# Arduino-Pro-Mini-RasPi.net
KiCad netlist of a schematic drawn in EAGLE
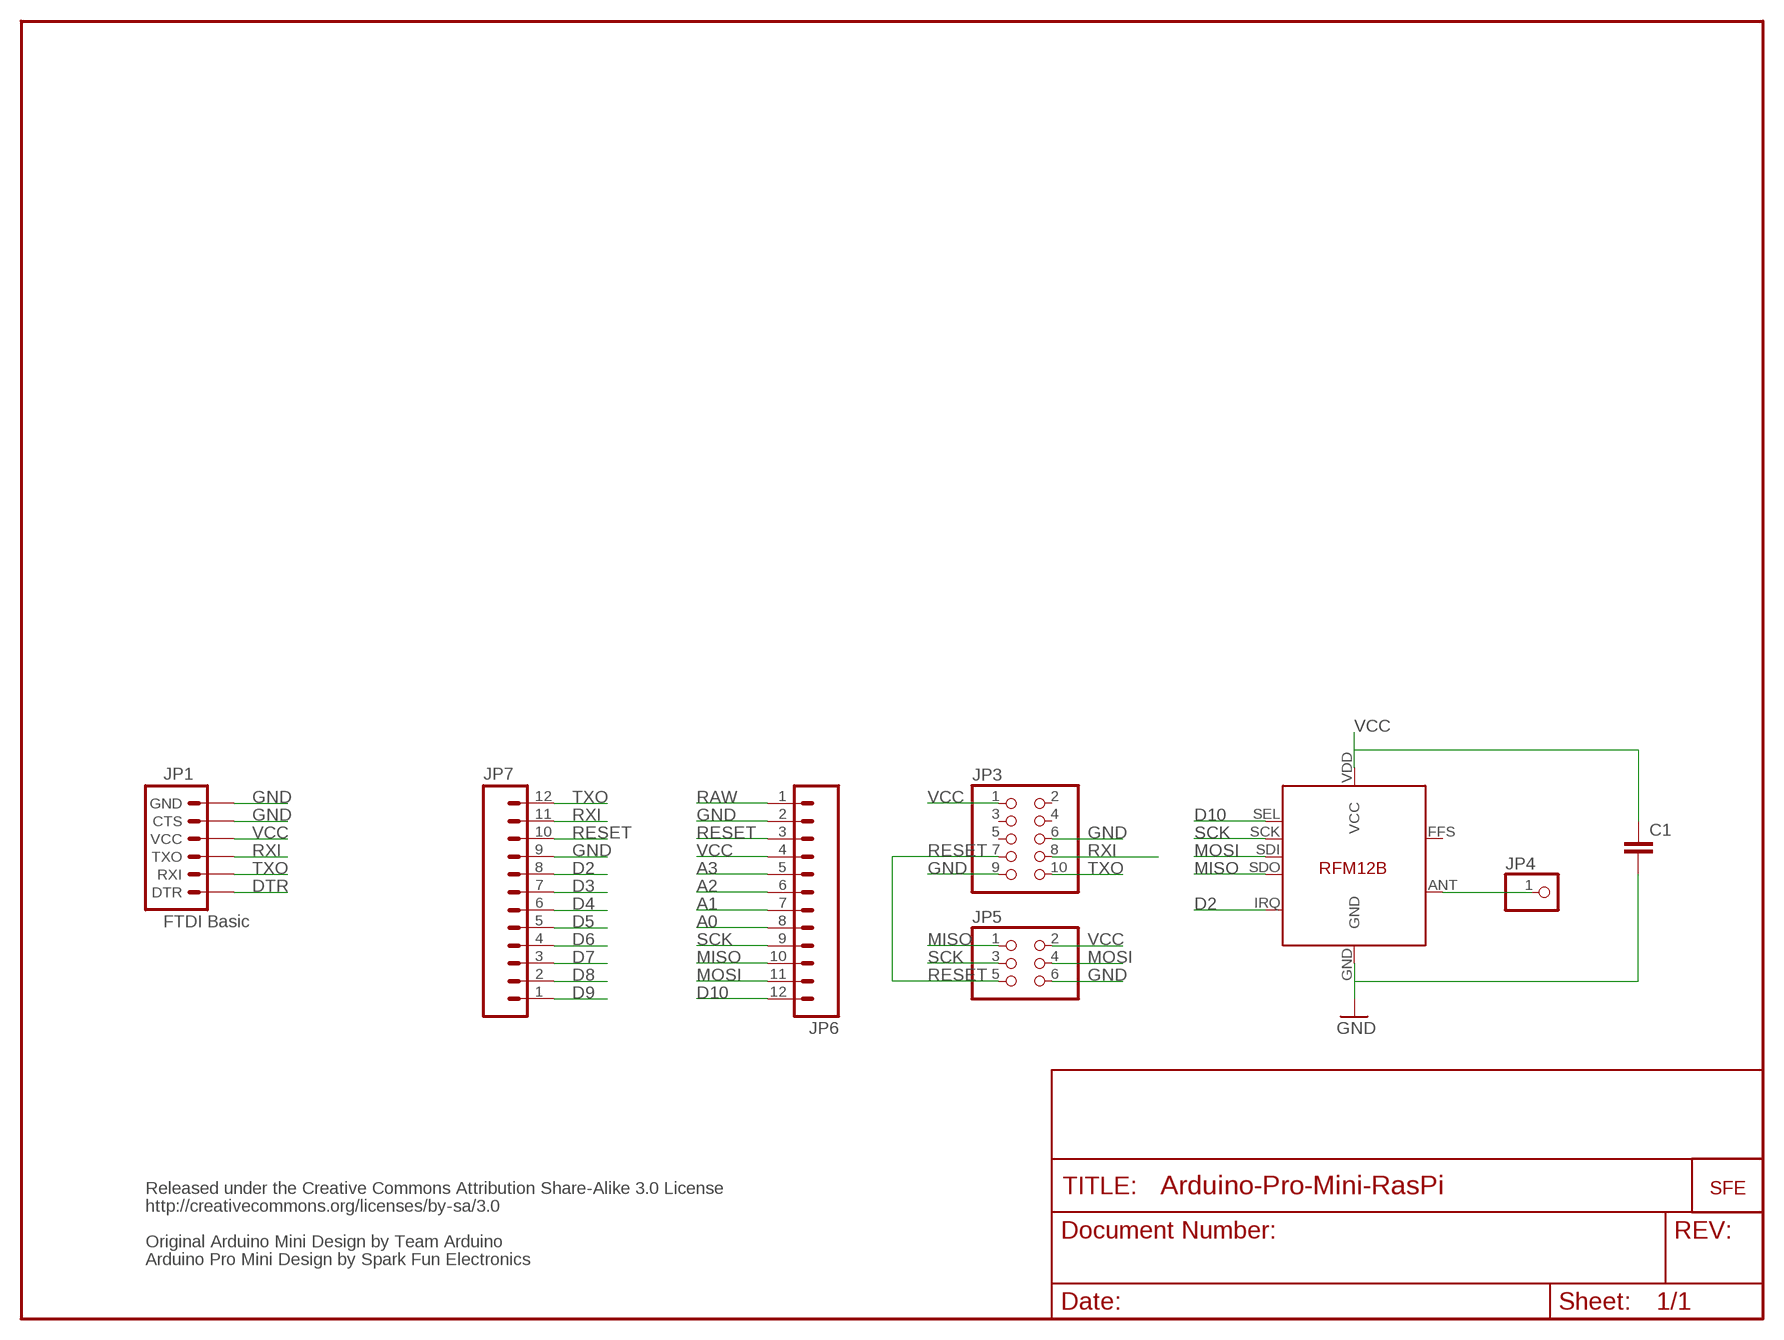
[diagram p0: schematic, sheet 1]

(export (version "E")
  (design (tool "Eeschema 10.0.6"))
  (components
    (comp (ref "C1")
      (value "C-EUC0805K")
      (footprint "eagle-import:C0805K")
      (libsource (lib "eagle-import") (part "C-EUC0805K"))
    )
    (comp (ref "JP1")
      (value "FTDI Basic")
      (footprint "eagle-import:1X06")
      (libsource (lib "eagle-import") (part "ARDUINO_SERIAL_PROGRAMPTH"))
    )
    (comp (ref "JP3")
      (value "PINHD-2X5")
      (footprint "eagle-import:2X05")
      (libsource (lib "eagle-import") (part "PINHD-2X5"))
    )
    (comp (ref "JP4")
      (value "PINHD-1X1")
      (footprint "eagle-import:1X01")
      (libsource (lib "eagle-import") (part "PINHD-1X1"))
    )
    (comp (ref "JP5")
      (value "PINHD-2X3_2.54-SMD")
      (footprint "eagle-import:2X03SMD")
      (libsource (lib "eagle-import") (part "PINHD-2X3_2.54-SMD"))
    )
    (comp (ref "JP6")
      (value "M12PTH")
      (footprint "eagle-import:1X12")
      (libsource (lib "eagle-import") (part "M12PTH"))
    )
    (comp (ref "JP7")
      (value "M12PTH")
      (footprint "eagle-import:1X12")
      (libsource (lib "eagle-import") (part "M12PTH"))
    )
    (comp (ref "U$3")
      (value "RFM12B")
      (footprint "eagle-import:RFM12B")
      (libsource (lib "eagle-import") (part "RFM12B"))
    )
    (comp (ref "U$11")
      (value "LOGO-SFENEW")
      (footprint "eagle-import:SFE-NEW-WEBLOGO")
      (libsource (lib "eagle-import") (part "LOGO-SFENEW"))
    )
  )
  (nets
    (net (code "1") (name "/A0") (class "Default")
      (node (ref "JP6") (pin "8") (pinfunction "8_8") (pintype "passive"))
    )
    (net (code "2") (name "/A1") (class "Default")
      (node (ref "JP6") (pin "7") (pinfunction "7_7") (pintype "passive"))
    )
    (net (code "3") (name "/A2") (class "Default")
      (node (ref "JP6") (pin "6") (pinfunction "6_6") (pintype "passive"))
    )
    (net (code "4") (name "/A3") (class "Default")
      (node (ref "JP6") (pin "5") (pinfunction "5_5") (pintype "passive"))
    )
    (net (code "5") (name "/D2") (class "Default")
      (node (ref "JP7") (pin "8") (pinfunction "8_8") (pintype "passive"))
      (node (ref "U$3") (pin "IRQ") (pinfunction "IRQ_IRQ") (pintype "open_collector"))
    )
    (net (code "6") (name "/D3") (class "Default")
      (node (ref "JP7") (pin "7") (pinfunction "7_7") (pintype "passive"))
    )
    (net (code "7") (name "/D4") (class "Default")
      (node (ref "JP7") (pin "6") (pinfunction "6_6") (pintype "passive"))
    )
    (net (code "8") (name "/D5") (class "Default")
      (node (ref "JP7") (pin "5") (pinfunction "5_5") (pintype "passive"))
    )
    (net (code "9") (name "/D6") (class "Default")
      (node (ref "JP7") (pin "4") (pinfunction "4_4") (pintype "passive"))
    )
    (net (code "10") (name "/D7") (class "Default")
      (node (ref "JP7") (pin "3") (pinfunction "3_3") (pintype "passive"))
    )
    (net (code "11") (name "/D8") (class "Default")
      (node (ref "JP7") (pin "2") (pinfunction "2_2") (pintype "passive"))
    )
    (net (code "12") (name "/D9") (class "Default")
      (node (ref "JP7") (pin "1") (pinfunction "1_1") (pintype "passive"))
    )
    (net (code "13") (name "/D10") (class "Default")
      (node (ref "JP6") (pin "12") (pinfunction "12_12") (pintype "passive"))
      (node (ref "U$3") (pin "SEL") (pinfunction "SEL_SEL") (pintype "input"))
    )
    (net (code "14") (name "/DTR") (class "Default")
      (node (ref "JP1") (pin "1") (pinfunction "DTR_1") (pintype "passive"))
    )
    (net (code "15") (name "/MISO") (class "Default")
      (node (ref "JP5") (pin "1") (pinfunction "1_1") (pintype "passive"))
      (node (ref "JP6") (pin "10") (pinfunction "10_10") (pintype "passive"))
      (node (ref "U$3") (pin "SDO") (pinfunction "SDO_SDO") (pintype "output"))
    )
    (net (code "16") (name "/MOSI") (class "Default")
      (node (ref "JP5") (pin "4") (pinfunction "4_4") (pintype "passive"))
      (node (ref "JP6") (pin "11") (pinfunction "11_11") (pintype "passive"))
      (node (ref "U$3") (pin "SDI") (pinfunction "SDI_SDI") (pintype "input"))
    )
    (net (code "17") (name "/RAW") (class "Default")
      (node (ref "JP6") (pin "1") (pinfunction "1_1") (pintype "passive"))
    )
    (net (code "18") (name "/RESET") (class "Default")
      (node (ref "JP3") (pin "7") (pinfunction "7_7") (pintype "passive"))
      (node (ref "JP5") (pin "5") (pinfunction "5_5") (pintype "passive"))
      (node (ref "JP6") (pin "3") (pinfunction "3_3") (pintype "passive"))
      (node (ref "JP7") (pin "10") (pinfunction "10_10") (pintype "passive"))
    )
    (net (code "19") (name "/RXI") (class "Default")
      (node (ref "JP1") (pin "3") (pinfunction "TXO_3") (pintype "passive"))
      (node (ref "JP3") (pin "8") (pinfunction "8_8") (pintype "passive"))
      (node (ref "JP7") (pin "11") (pinfunction "11_11") (pintype "passive"))
    )
    (net (code "20") (name "/SCK") (class "Default")
      (node (ref "JP5") (pin "3") (pinfunction "3_3") (pintype "passive"))
      (node (ref "JP6") (pin "9") (pinfunction "9_9") (pintype "passive"))
      (node (ref "U$3") (pin "SCK") (pinfunction "SCK_SCK") (pintype "input"))
    )
    (net (code "21") (name "/TXO") (class "Default")
      (node (ref "JP1") (pin "2") (pinfunction "RXI_2") (pintype "passive"))
      (node (ref "JP3") (pin "10") (pinfunction "10_10") (pintype "passive"))
      (node (ref "JP7") (pin "12") (pinfunction "12_12") (pintype "passive"))
    )
    (net (code "22") (name "/VCC") (class "Default")
      (node (ref "C1") (pin "1") (pinfunction "1_1") (pintype "passive"))
      (node (ref "JP1") (pin "4") (pinfunction "VCC_4") (pintype "passive"))
      (node (ref "JP3") (pin "1") (pinfunction "1_1") (pintype "passive"))
      (node (ref "JP5") (pin "2") (pinfunction "2_2") (pintype "passive"))
      (node (ref "JP6") (pin "4") (pinfunction "4_4") (pintype "passive"))
      (node (ref "U$3") (pin "VDD") (pinfunction "VCC_VDD") (pintype "power_in"))
    )
    (net (code "23") (name "GND") (class "Default")
      (node (ref "C1") (pin "2") (pinfunction "2_2") (pintype "passive"))
      (node (ref "JP1") (pin "5") (pinfunction "CTS_5") (pintype "passive"))
      (node (ref "JP1") (pin "6") (pinfunction "GND_6") (pintype "passive"))
      (node (ref "JP3") (pin "6") (pinfunction "6_6") (pintype "passive"))
      (node (ref "JP3") (pin "9") (pinfunction "9_9") (pintype "passive"))
      (node (ref "JP5") (pin "6") (pinfunction "6_6") (pintype "passive"))
      (node (ref "JP6") (pin "2") (pinfunction "2_2") (pintype "passive"))
      (node (ref "JP7") (pin "9") (pinfunction "9_9") (pintype "passive"))
      (node (ref "U$3") (pin "GND") (pinfunction "GND_GND") (pintype "power_in"))
    )
    (net (code "24") (name "Net-(JP4-Pad1)") (class "Default")
      (node (ref "JP4") (pin "1") (pinfunction "1_1") (pintype "passive"))
      (node (ref "U$3") (pin "ANT") (pinfunction "ANT_ANT") (pintype "passive"))
    )
    (net (code "25") (name "unconnected-(JP3-Pad2)") (class "Default")
      (node (ref "JP3") (pin "2") (pinfunction "2_2") (pintype "passive"))
    )
    (net (code "26") (name "unconnected-(JP3-Pad3)") (class "Default")
      (node (ref "JP3") (pin "3") (pinfunction "3_3") (pintype "passive"))
    )
    (net (code "27") (name "unconnected-(JP3-Pad4)") (class "Default")
      (node (ref "JP3") (pin "4") (pinfunction "4_4") (pintype "passive"))
    )
    (net (code "28") (name "unconnected-(JP3-Pad5)") (class "Default")
      (node (ref "JP3") (pin "5") (pinfunction "5_5") (pintype "passive"))
    )
    (net (code "29") (name "unconnected-(U$3-PadFFS)") (class "Default")
      (node (ref "U$3") (pin "FFS") (pinfunction "FFS_FFS") (pintype "bidirectional"))
    )
  )
)
